# DRV_04_25_2017.net
KiCad netlist of a schematic drawn in EAGLE
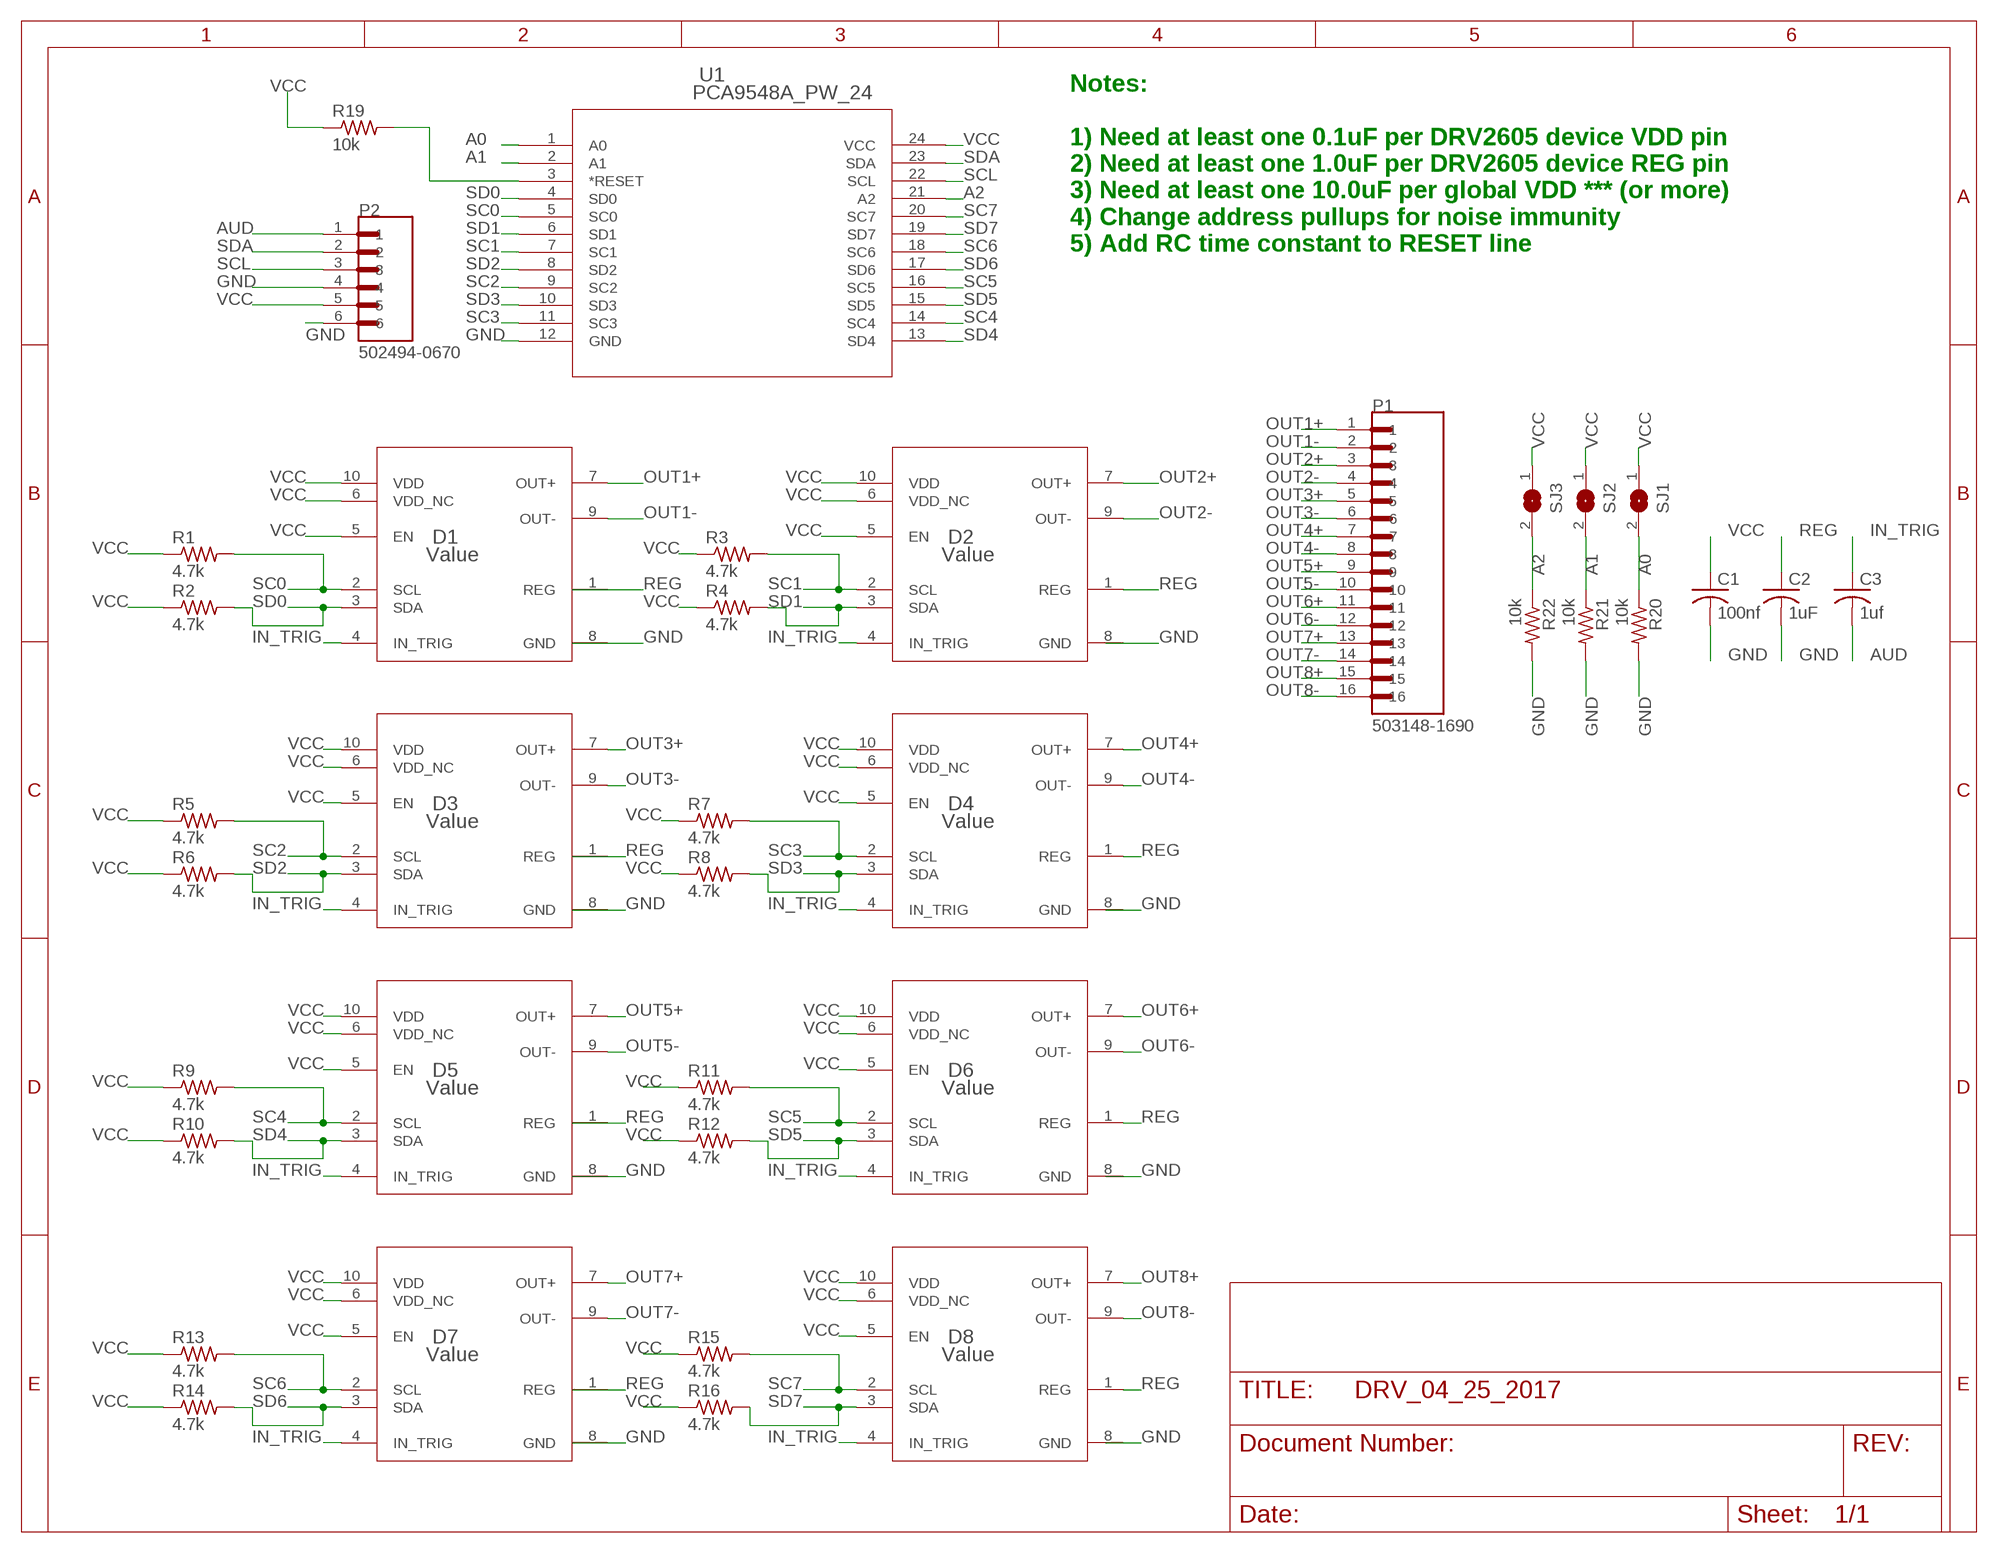
[diagram p0: schematic, sheet 1]

(export (version "E")
  (design (tool "Eeschema 10.0.6"))
  (components
    (comp (ref "C1")
      (value "100nf")
      (footprint "eagle-import:C0603")
      (libsource (lib "eagle-import") (part "C-USC0603"))
    )
    (comp (ref "C2")
      (value "1uF")
      (footprint "eagle-import:C0603")
      (libsource (lib "eagle-import") (part "C-USC0603"))
    )
    (comp (ref "C3")
      (value "1uf")
      (footprint "eagle-import:C0603")
      (libsource (lib "eagle-import") (part "C-USC0603"))
    )
    (comp (ref "D1")
      (value "Value")
      (footprint "eagle-import:DGS0010A")
      (fields (field (name "MANUFACTURER") "Texas Instruments") (field (name "PARTNUMBER") "DRV2605LDGS"))
      (libsource (lib "eagle-import") (part "DRV2605LDGSR"))
    )
    (comp (ref "D2")
      (value "Value")
      (footprint "eagle-import:DGS0010A")
      (fields (field (name "MANUFACTURER") "Texas Instruments") (field (name "PARTNUMBER") "DRV2605LDGS"))
      (libsource (lib "eagle-import") (part "DRV2605LDGSR"))
    )
    (comp (ref "D3")
      (value "Value")
      (footprint "eagle-import:DGS0010A")
      (fields (field (name "MANUFACTURER") "Texas Instruments") (field (name "PARTNUMBER") "DRV2605LDGS"))
      (libsource (lib "eagle-import") (part "DRV2605LDGSR"))
    )
    (comp (ref "D4")
      (value "Value")
      (footprint "eagle-import:DGS0010A")
      (fields (field (name "MANUFACTURER") "Texas Instruments") (field (name "PARTNUMBER") "DRV2605LDGS"))
      (libsource (lib "eagle-import") (part "DRV2605LDGSR"))
    )
    (comp (ref "D5")
      (value "Value")
      (footprint "eagle-import:DGS0010A")
      (fields (field (name "MANUFACTURER") "Texas Instruments") (field (name "PARTNUMBER") "DRV2605LDGS"))
      (libsource (lib "eagle-import") (part "DRV2605LDGSR"))
    )
    (comp (ref "D6")
      (value "Value")
      (footprint "eagle-import:DGS0010A")
      (fields (field (name "MANUFACTURER") "Texas Instruments") (field (name "PARTNUMBER") "DRV2605LDGS"))
      (libsource (lib "eagle-import") (part "DRV2605LDGSR"))
    )
    (comp (ref "D7")
      (value "Value")
      (footprint "eagle-import:DGS0010A")
      (fields (field (name "MANUFACTURER") "Texas Instruments") (field (name "PARTNUMBER") "DRV2605LDGS"))
      (libsource (lib "eagle-import") (part "DRV2605LDGSR"))
    )
    (comp (ref "D8")
      (value "Value")
      (footprint "eagle-import:DGS0010A")
      (fields (field (name "MANUFACTURER") "Texas Instruments") (field (name "PARTNUMBER") "DRV2605LDGS"))
      (libsource (lib "eagle-import") (part "DRV2605LDGSR"))
    )
    (comp (ref "P1")
      (value "503148-1690")
      (footprint "eagle-import:MOLEX_503148-1690")
      (fields (field (name "MF") "Molex"))
      (libsource (lib "eagle-import") (part "503148-1690"))
    )
    (comp (ref "P2")
      (value "502494-0670")
      (footprint "eagle-import:MOLEX_502494-0670")
      (fields (field (name "MF") "Molex"))
      (libsource (lib "eagle-import") (part "502494-0670"))
    )
    (comp (ref "R1")
      (value "4.7k")
      (footprint "eagle-import:R0402")
      (libsource (lib "eagle-import") (part "R-US_R0402"))
    )
    (comp (ref "R2")
      (value "4.7k")
      (footprint "eagle-import:R0402")
      (libsource (lib "eagle-import") (part "R-US_R0402"))
    )
    (comp (ref "R3")
      (value "4.7k")
      (footprint "eagle-import:R0402")
      (libsource (lib "eagle-import") (part "R-US_R0402"))
    )
    (comp (ref "R4")
      (value "4.7k")
      (footprint "eagle-import:R0402")
      (libsource (lib "eagle-import") (part "R-US_R0402"))
    )
    (comp (ref "R5")
      (value "4.7k")
      (footprint "eagle-import:R0402")
      (libsource (lib "eagle-import") (part "R-US_R0402"))
    )
    (comp (ref "R6")
      (value "4.7k")
      (footprint "eagle-import:R0402")
      (libsource (lib "eagle-import") (part "R-US_R0402"))
    )
    (comp (ref "R7")
      (value "4.7k")
      (footprint "eagle-import:R0402")
      (libsource (lib "eagle-import") (part "R-US_R0402"))
    )
    (comp (ref "R8")
      (value "4.7k")
      (footprint "eagle-import:R0402")
      (libsource (lib "eagle-import") (part "R-US_R0402"))
    )
    (comp (ref "R9")
      (value "4.7k")
      (footprint "eagle-import:R0402")
      (libsource (lib "eagle-import") (part "R-US_R0402"))
    )
    (comp (ref "R10")
      (value "4.7k")
      (footprint "eagle-import:R0402")
      (libsource (lib "eagle-import") (part "R-US_R0402"))
    )
    (comp (ref "R11")
      (value "4.7k")
      (footprint "eagle-import:R0402")
      (libsource (lib "eagle-import") (part "R-US_R0402"))
    )
    (comp (ref "R12")
      (value "4.7k")
      (footprint "eagle-import:R0402")
      (libsource (lib "eagle-import") (part "R-US_R0402"))
    )
    (comp (ref "R13")
      (value "4.7k")
      (footprint "eagle-import:R0402")
      (libsource (lib "eagle-import") (part "R-US_R0402"))
    )
    (comp (ref "R14")
      (value "4.7k")
      (footprint "eagle-import:R0402")
      (libsource (lib "eagle-import") (part "R-US_R0402"))
    )
    (comp (ref "R15")
      (value "4.7k")
      (footprint "eagle-import:R0402")
      (libsource (lib "eagle-import") (part "R-US_R0402"))
    )
    (comp (ref "R16")
      (value "4.7k")
      (footprint "eagle-import:R0402")
      (libsource (lib "eagle-import") (part "R-US_R0402"))
    )
    (comp (ref "R19")
      (value "10k")
      (footprint "eagle-import:R0402")
      (libsource (lib "eagle-import") (part "R-US_R0402"))
    )
    (comp (ref "R20")
      (value "10k")
      (footprint "eagle-import:R0402")
      (libsource (lib "eagle-import") (part "R-US_R0402"))
    )
    (comp (ref "R21")
      (value "10k")
      (footprint "eagle-import:R0402")
      (libsource (lib "eagle-import") (part "R-US_R0402"))
    )
    (comp (ref "R22")
      (value "10k")
      (footprint "eagle-import:R0402")
      (libsource (lib "eagle-import") (part "R-US_R0402"))
    )
    (comp (ref "SJ1") (value "SJ") (footprint "eagle-import:SJ") (libsource (lib "eagle-import") (part "SJ")))
    (comp (ref "SJ2") (value "SJ") (footprint "eagle-import:SJ") (libsource (lib "eagle-import") (part "SJ")))
    (comp (ref "SJ3") (value "SJ") (footprint "eagle-import:SJ") (libsource (lib "eagle-import") (part "SJ")))
    (comp (ref "U1")
      (value "PCA9548A_PW_24")
      (footprint "eagle-import:PW24")
      (fields
        (field (name "GENERIC_PART_NUMBER") "PCA9548A")
        (field (name "MANUFACTURER") "Texas Instruments")
        (field (name "MANUFACTURER_PART_NUMBER") "pca9548a_pw_24")
      )
      (libsource (lib "eagle-import") (part "PCA9548A_PW_24"))
    )
  )
  (nets
    (net (code "1") (name "/A0") (class "Default")
      (node (ref "R20") (pin "1") (pinfunction "1_1") (pintype "passive"))
      (node (ref "SJ1") (pin "2") (pinfunction "2_2") (pintype "passive"))
      (node (ref "U1") (pin "1") (pinfunction "A0_1") (pintype "input"))
    )
    (net (code "2") (name "/A1") (class "Default")
      (node (ref "R21") (pin "1") (pinfunction "1_1") (pintype "passive"))
      (node (ref "SJ2") (pin "2") (pinfunction "2_2") (pintype "passive"))
      (node (ref "U1") (pin "2") (pinfunction "A1_2") (pintype "input"))
    )
    (net (code "3") (name "/A2") (class "Default")
      (node (ref "R22") (pin "1") (pinfunction "1_1") (pintype "passive"))
      (node (ref "SJ3") (pin "2") (pinfunction "2_2") (pintype "passive"))
      (node (ref "U1") (pin "21") (pinfunction "A2_21") (pintype "input"))
    )
    (net (code "4") (name "/AUD") (class "Default")
      (node (ref "C3") (pin "2") (pinfunction "2_2") (pintype "passive"))
      (node (ref "P2") (pin "1") (pinfunction "1_1") (pintype "passive"))
    )
    (net (code "5") (name "/GND") (class "Default")
      (node (ref "C1") (pin "2") (pinfunction "2_2") (pintype "passive"))
      (node (ref "C2") (pin "2") (pinfunction "2_2") (pintype "passive"))
      (node (ref "D1") (pin "8") (pinfunction "GND_8") (pintype "power_in"))
      (node (ref "D2") (pin "8") (pinfunction "GND_8") (pintype "power_in"))
      (node (ref "D3") (pin "8") (pinfunction "GND_8") (pintype "power_in"))
      (node (ref "D4") (pin "8") (pinfunction "GND_8") (pintype "power_in"))
      (node (ref "D5") (pin "8") (pinfunction "GND_8") (pintype "power_in"))
      (node (ref "D6") (pin "8") (pinfunction "GND_8") (pintype "power_in"))
      (node (ref "D7") (pin "8") (pinfunction "GND_8") (pintype "power_in"))
      (node (ref "D8") (pin "8") (pinfunction "GND_8") (pintype "power_in"))
      (node (ref "P2") (pin "4") (pinfunction "4_4") (pintype "passive"))
      (node (ref "P2") (pin "6") (pinfunction "6_6") (pintype "passive"))
      (node (ref "R20") (pin "2") (pinfunction "2_2") (pintype "passive"))
      (node (ref "R21") (pin "2") (pinfunction "2_2") (pintype "passive"))
      (node (ref "R22") (pin "2") (pinfunction "2_2") (pintype "passive"))
      (node (ref "U1") (pin "12") (pinfunction "GND_12") (pintype "power_in"))
    )
    (net (code "6") (name "/IN_TRIG") (class "Default")
      (node (ref "C3") (pin "1") (pinfunction "1_1") (pintype "passive"))
      (node (ref "D1") (pin "4") (pinfunction "IN_TRIG_4") (pintype "input"))
      (node (ref "D2") (pin "4") (pinfunction "IN_TRIG_4") (pintype "input"))
      (node (ref "D3") (pin "4") (pinfunction "IN_TRIG_4") (pintype "input"))
      (node (ref "D4") (pin "4") (pinfunction "IN_TRIG_4") (pintype "input"))
      (node (ref "D5") (pin "4") (pinfunction "IN_TRIG_4") (pintype "input"))
      (node (ref "D6") (pin "4") (pinfunction "IN_TRIG_4") (pintype "input"))
      (node (ref "D7") (pin "4") (pinfunction "IN_TRIG_4") (pintype "input"))
      (node (ref "D8") (pin "4") (pinfunction "IN_TRIG_4") (pintype "input"))
    )
    (net (code "7") (name "/OUT1+") (class "Default")
      (node (ref "D1") (pin "7") (pinfunction "OUT+_7") (pintype "output"))
      (node (ref "P1") (pin "1") (pinfunction "1_1") (pintype "passive"))
    )
    (net (code "8") (name "/OUT1-") (class "Default")
      (node (ref "D1") (pin "9") (pinfunction "OUT-_9") (pintype "output"))
      (node (ref "P1") (pin "2") (pinfunction "2_2") (pintype "passive"))
    )
    (net (code "9") (name "/OUT2+") (class "Default")
      (node (ref "D2") (pin "7") (pinfunction "OUT+_7") (pintype "output"))
      (node (ref "P1") (pin "3") (pinfunction "3_3") (pintype "passive"))
    )
    (net (code "10") (name "/OUT2-") (class "Default")
      (node (ref "D2") (pin "9") (pinfunction "OUT-_9") (pintype "output"))
      (node (ref "P1") (pin "4") (pinfunction "4_4") (pintype "passive"))
    )
    (net (code "11") (name "/OUT3+") (class "Default")
      (node (ref "D3") (pin "7") (pinfunction "OUT+_7") (pintype "output"))
      (node (ref "P1") (pin "5") (pinfunction "5_5") (pintype "passive"))
    )
    (net (code "12") (name "/OUT3-") (class "Default")
      (node (ref "D3") (pin "9") (pinfunction "OUT-_9") (pintype "output"))
      (node (ref "P1") (pin "6") (pinfunction "6_6") (pintype "passive"))
    )
    (net (code "13") (name "/OUT4+") (class "Default")
      (node (ref "D4") (pin "7") (pinfunction "OUT+_7") (pintype "output"))
      (node (ref "P1") (pin "7") (pinfunction "7_7") (pintype "passive"))
    )
    (net (code "14") (name "/OUT4-") (class "Default")
      (node (ref "D4") (pin "9") (pinfunction "OUT-_9") (pintype "output"))
      (node (ref "P1") (pin "8") (pinfunction "8_8") (pintype "passive"))
    )
    (net (code "15") (name "/OUT5+") (class "Default")
      (node (ref "D5") (pin "7") (pinfunction "OUT+_7") (pintype "output"))
      (node (ref "P1") (pin "9") (pinfunction "9_9") (pintype "passive"))
    )
    (net (code "16") (name "/OUT5-") (class "Default")
      (node (ref "D5") (pin "9") (pinfunction "OUT-_9") (pintype "output"))
      (node (ref "P1") (pin "10") (pinfunction "10_10") (pintype "passive"))
    )
    (net (code "17") (name "/OUT6+") (class "Default")
      (node (ref "D6") (pin "7") (pinfunction "OUT+_7") (pintype "output"))
      (node (ref "P1") (pin "11") (pinfunction "11_11") (pintype "passive"))
    )
    (net (code "18") (name "/OUT6-") (class "Default")
      (node (ref "D6") (pin "9") (pinfunction "OUT-_9") (pintype "output"))
      (node (ref "P1") (pin "12") (pinfunction "12_12") (pintype "passive"))
    )
    (net (code "19") (name "/OUT7+") (class "Default")
      (node (ref "D7") (pin "7") (pinfunction "OUT+_7") (pintype "output"))
      (node (ref "P1") (pin "13") (pinfunction "13_13") (pintype "passive"))
    )
    (net (code "20") (name "/OUT7-") (class "Default")
      (node (ref "D7") (pin "9") (pinfunction "OUT-_9") (pintype "output"))
      (node (ref "P1") (pin "14") (pinfunction "14_14") (pintype "passive"))
    )
    (net (code "21") (name "/OUT8+") (class "Default")
      (node (ref "D8") (pin "7") (pinfunction "OUT+_7") (pintype "output"))
      (node (ref "P1") (pin "15") (pinfunction "15_15") (pintype "passive"))
    )
    (net (code "22") (name "/OUT8-") (class "Default")
      (node (ref "D8") (pin "9") (pinfunction "OUT-_9") (pintype "output"))
      (node (ref "P1") (pin "16") (pinfunction "16_16") (pintype "passive"))
    )
    (net (code "23") (name "/REG") (class "Default")
      (node (ref "C2") (pin "1") (pinfunction "1_1") (pintype "passive"))
      (node (ref "D1") (pin "1") (pinfunction "REG_1") (pintype "power_in"))
      (node (ref "D2") (pin "1") (pinfunction "REG_1") (pintype "power_in"))
      (node (ref "D3") (pin "1") (pinfunction "REG_1") (pintype "power_in"))
      (node (ref "D4") (pin "1") (pinfunction "REG_1") (pintype "power_in"))
      (node (ref "D5") (pin "1") (pinfunction "REG_1") (pintype "power_in"))
      (node (ref "D6") (pin "1") (pinfunction "REG_1") (pintype "power_in"))
      (node (ref "D7") (pin "1") (pinfunction "REG_1") (pintype "power_in"))
      (node (ref "D8") (pin "1") (pinfunction "REG_1") (pintype "power_in"))
    )
    (net (code "24") (name "/SC0") (class "Default")
      (node (ref "D1") (pin "2") (pinfunction "SCL_2") (pintype "input"))
      (node (ref "R1") (pin "2") (pinfunction "2_2") (pintype "passive"))
      (node (ref "U1") (pin "5") (pinfunction "SC0_5") (pintype "passive"))
    )
    (net (code "25") (name "/SC1") (class "Default")
      (node (ref "D2") (pin "2") (pinfunction "SCL_2") (pintype "input"))
      (node (ref "R3") (pin "2") (pinfunction "2_2") (pintype "passive"))
      (node (ref "U1") (pin "7") (pinfunction "SC1_7") (pintype "passive"))
    )
    (net (code "26") (name "/SC2") (class "Default")
      (node (ref "D3") (pin "2") (pinfunction "SCL_2") (pintype "input"))
      (node (ref "R5") (pin "2") (pinfunction "2_2") (pintype "passive"))
      (node (ref "U1") (pin "9") (pinfunction "SC2_9") (pintype "passive"))
    )
    (net (code "27") (name "/SC3") (class "Default")
      (node (ref "D4") (pin "2") (pinfunction "SCL_2") (pintype "input"))
      (node (ref "R7") (pin "2") (pinfunction "2_2") (pintype "passive"))
      (node (ref "U1") (pin "11") (pinfunction "SC3_11") (pintype "passive"))
    )
    (net (code "28") (name "/SC4") (class "Default")
      (node (ref "D5") (pin "2") (pinfunction "SCL_2") (pintype "input"))
      (node (ref "R9") (pin "2") (pinfunction "2_2") (pintype "passive"))
      (node (ref "U1") (pin "14") (pinfunction "SC4_14") (pintype "passive"))
    )
    (net (code "29") (name "/SC5") (class "Default")
      (node (ref "D6") (pin "2") (pinfunction "SCL_2") (pintype "input"))
      (node (ref "R11") (pin "2") (pinfunction "2_2") (pintype "passive"))
      (node (ref "U1") (pin "16") (pinfunction "SC5_16") (pintype "passive"))
    )
    (net (code "30") (name "/SC6") (class "Default")
      (node (ref "D7") (pin "2") (pinfunction "SCL_2") (pintype "input"))
      (node (ref "R13") (pin "2") (pinfunction "2_2") (pintype "passive"))
      (node (ref "U1") (pin "18") (pinfunction "SC6_18") (pintype "passive"))
    )
    (net (code "31") (name "/SC7") (class "Default")
      (node (ref "D8") (pin "2") (pinfunction "SCL_2") (pintype "input"))
      (node (ref "R15") (pin "2") (pinfunction "2_2") (pintype "passive"))
      (node (ref "U1") (pin "20") (pinfunction "SC7_20") (pintype "passive"))
    )
    (net (code "32") (name "/SCL") (class "Default")
      (node (ref "P2") (pin "3") (pinfunction "3_3") (pintype "passive"))
      (node (ref "U1") (pin "22") (pinfunction "SCL_22") (pintype "passive"))
    )
    (net (code "33") (name "/SD0") (class "Default")
      (node (ref "D1") (pin "3") (pinfunction "SDA_3") (pintype "bidirectional"))
      (node (ref "R2") (pin "2") (pinfunction "2_2") (pintype "passive"))
      (node (ref "U1") (pin "4") (pinfunction "SD0_4") (pintype "passive"))
    )
    (net (code "34") (name "/SD1") (class "Default")
      (node (ref "D2") (pin "3") (pinfunction "SDA_3") (pintype "bidirectional"))
      (node (ref "R4") (pin "2") (pinfunction "2_2") (pintype "passive"))
      (node (ref "U1") (pin "6") (pinfunction "SD1_6") (pintype "passive"))
    )
    (net (code "35") (name "/SD2") (class "Default")
      (node (ref "D3") (pin "3") (pinfunction "SDA_3") (pintype "bidirectional"))
      (node (ref "R6") (pin "2") (pinfunction "2_2") (pintype "passive"))
      (node (ref "U1") (pin "8") (pinfunction "SD2_8") (pintype "passive"))
    )
    (net (code "36") (name "/SD3") (class "Default")
      (node (ref "D4") (pin "3") (pinfunction "SDA_3") (pintype "bidirectional"))
      (node (ref "R8") (pin "2") (pinfunction "2_2") (pintype "passive"))
      (node (ref "U1") (pin "10") (pinfunction "SD3_10") (pintype "passive"))
    )
    (net (code "37") (name "/SD4") (class "Default")
      (node (ref "D5") (pin "3") (pinfunction "SDA_3") (pintype "bidirectional"))
      (node (ref "R10") (pin "2") (pinfunction "2_2") (pintype "passive"))
      (node (ref "U1") (pin "13") (pinfunction "SD4_13") (pintype "passive"))
    )
    (net (code "38") (name "/SD5") (class "Default")
      (node (ref "D6") (pin "3") (pinfunction "SDA_3") (pintype "bidirectional"))
      (node (ref "R12") (pin "2") (pinfunction "2_2") (pintype "passive"))
      (node (ref "U1") (pin "15") (pinfunction "SD5_15") (pintype "passive"))
    )
    (net (code "39") (name "/SD6") (class "Default")
      (node (ref "D7") (pin "3") (pinfunction "SDA_3") (pintype "bidirectional"))
      (node (ref "R14") (pin "2") (pinfunction "2_2") (pintype "passive"))
      (node (ref "U1") (pin "17") (pinfunction "SD6_17") (pintype "passive"))
    )
    (net (code "40") (name "/SD7") (class "Default")
      (node (ref "D8") (pin "3") (pinfunction "SDA_3") (pintype "bidirectional"))
      (node (ref "R16") (pin "2") (pinfunction "2_2") (pintype "passive"))
      (node (ref "U1") (pin "19") (pinfunction "SD7_19") (pintype "passive"))
    )
    (net (code "41") (name "/SDA") (class "Default")
      (node (ref "P2") (pin "2") (pinfunction "2_2") (pintype "passive"))
      (node (ref "U1") (pin "23") (pinfunction "SDA_23") (pintype "passive"))
    )
    (net (code "42") (name "/VCC") (class "Default")
      (node (ref "C1") (pin "1") (pinfunction "1_1") (pintype "passive"))
      (node (ref "D1") (pin "10") (pinfunction "VDD_10") (pintype "power_in"))
      (node (ref "D1") (pin "5") (pinfunction "EN_5") (pintype "input"))
      (node (ref "D1") (pin "6") (pinfunction "VDD_NC_6") (pintype "power_in"))
      (node (ref "D2") (pin "10") (pinfunction "VDD_10") (pintype "power_in"))
      (node (ref "D2") (pin "5") (pinfunction "EN_5") (pintype "input"))
      (node (ref "D2") (pin "6") (pinfunction "VDD_NC_6") (pintype "power_in"))
      (node (ref "D3") (pin "10") (pinfunction "VDD_10") (pintype "power_in"))
      (node (ref "D3") (pin "5") (pinfunction "EN_5") (pintype "input"))
      (node (ref "D3") (pin "6") (pinfunction "VDD_NC_6") (pintype "power_in"))
      (node (ref "D4") (pin "10") (pinfunction "VDD_10") (pintype "power_in"))
      (node (ref "D4") (pin "5") (pinfunction "EN_5") (pintype "input"))
      (node (ref "D4") (pin "6") (pinfunction "VDD_NC_6") (pintype "power_in"))
      (node (ref "D5") (pin "10") (pinfunction "VDD_10") (pintype "power_in"))
      (node (ref "D5") (pin "5") (pinfunction "EN_5") (pintype "input"))
      (node (ref "D5") (pin "6") (pinfunction "VDD_NC_6") (pintype "power_in"))
      (node (ref "D6") (pin "10") (pinfunction "VDD_10") (pintype "power_in"))
      (node (ref "D6") (pin "5") (pinfunction "EN_5") (pintype "input"))
      (node (ref "D6") (pin "6") (pinfunction "VDD_NC_6") (pintype "power_in"))
      (node (ref "D7") (pin "10") (pinfunction "VDD_10") (pintype "power_in"))
      (node (ref "D7") (pin "5") (pinfunction "EN_5") (pintype "input"))
      (node (ref "D7") (pin "6") (pinfunction "VDD_NC_6") (pintype "power_in"))
      (node (ref "D8") (pin "10") (pinfunction "VDD_10") (pintype "power_in"))
      (node (ref "D8") (pin "5") (pinfunction "EN_5") (pintype "input"))
      (node (ref "D8") (pin "6") (pinfunction "VDD_NC_6") (pintype "power_in"))
      (node (ref "P2") (pin "5") (pinfunction "5_5") (pintype "passive"))
      (node (ref "R1") (pin "1") (pinfunction "1_1") (pintype "passive"))
      (node (ref "R10") (pin "1") (pinfunction "1_1") (pintype "passive"))
      (node (ref "R11") (pin "1") (pinfunction "1_1") (pintype "passive"))
      (node (ref "R12") (pin "1") (pinfunction "1_1") (pintype "passive"))
      (node (ref "R13") (pin "1") (pinfunction "1_1") (pintype "passive"))
      (node (ref "R14") (pin "1") (pinfunction "1_1") (pintype "passive"))
      (node (ref "R15") (pin "1") (pinfunction "1_1") (pintype "passive"))
      (node (ref "R16") (pin "1") (pinfunction "1_1") (pintype "passive"))
      (node (ref "R19") (pin "1") (pinfunction "1_1") (pintype "passive"))
      (node (ref "R2") (pin "1") (pinfunction "1_1") (pintype "passive"))
      (node (ref "R3") (pin "1") (pinfunction "1_1") (pintype "passive"))
      (node (ref "R4") (pin "1") (pinfunction "1_1") (pintype "passive"))
      (node (ref "R5") (pin "1") (pinfunction "1_1") (pintype "passive"))
      (node (ref "R6") (pin "1") (pinfunction "1_1") (pintype "passive"))
      (node (ref "R7") (pin "1") (pinfunction "1_1") (pintype "passive"))
      (node (ref "R8") (pin "1") (pinfunction "1_1") (pintype "passive"))
      (node (ref "R9") (pin "1") (pinfunction "1_1") (pintype "passive"))
      (node (ref "SJ1") (pin "1") (pinfunction "1_1") (pintype "passive"))
      (node (ref "SJ2") (pin "1") (pinfunction "1_1") (pintype "passive"))
      (node (ref "SJ3") (pin "1") (pinfunction "1_1") (pintype "passive"))
      (node (ref "U1") (pin "24") (pinfunction "VCC_24") (pintype "power_in"))
    )
    (net (code "43") (name "Net-(U1-*RESET)") (class "Default")
      (node (ref "R19") (pin "2") (pinfunction "2_2") (pintype "passive"))
      (node (ref "U1") (pin "3") (pinfunction "*RESET_3") (pintype "input"))
    )
  )
)
